# led_button.net
KiCad netlist of a schematic drawn in EAGLE
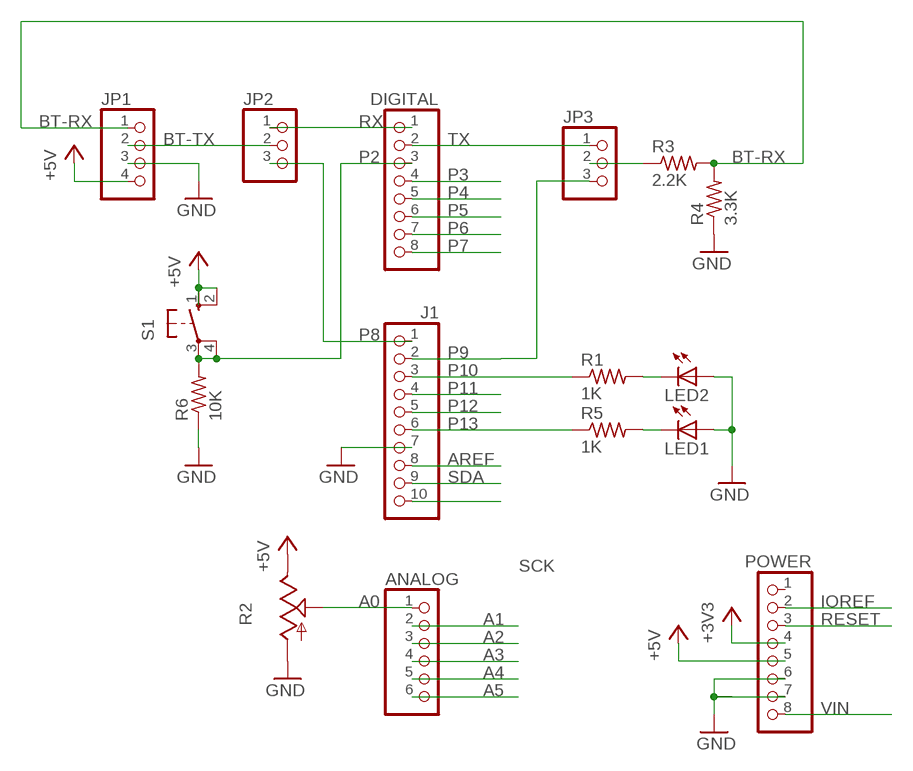
[diagram p0: schematic, sheet 1]

(export (version "E")
  (design (tool "Eeschema 10.0.6"))
  (components
    (comp (ref "ANALOG")
      (value "PINHD-1X6")
      (footprint "eagle-import:1X06")
      (libsource (lib "eagle-import") (part "PINHD-1X6"))
    )
    (comp (ref "DIGITAL")
      (value "PINHD-1X8TH")
      (footprint "eagle-import:1X08-TH")
      (libsource (lib "eagle-import") (part "PINHD-1X8TH"))
    )
    (comp (ref "J1")
      (value "PINHD-1X10TH")
      (footprint "eagle-import:1X10-TH")
      (libsource (lib "eagle-import") (part "PINHD-1X10TH"))
    )
    (comp (ref "JP1")
      (value "PINHD-1X4")
      (footprint "eagle-import:1X04")
      (libsource (lib "eagle-import") (part "PINHD-1X4"))
    )
    (comp (ref "JP2")
      (value "PINHD-1X3")
      (footprint "eagle-import:1X03")
      (libsource (lib "eagle-import") (part "PINHD-1X3"))
    )
    (comp (ref "JP3")
      (value "PINHD-1X3")
      (footprint "eagle-import:1X03")
      (libsource (lib "eagle-import") (part "PINHD-1X3"))
    )
    (comp (ref "LED1")
      (value "LED3MM")
      (footprint "eagle-import:LED3MM")
      (libsource (lib "eagle-import") (part "LED3MM"))
    )
    (comp (ref "LED2")
      (value "LED3MM")
      (footprint "eagle-import:LED3MM")
      (libsource (lib "eagle-import") (part "LED3MM"))
    )
    (comp (ref "POWER")
      (value "PINHD-1X8TH")
      (footprint "eagle-import:1X08-TH")
      (libsource (lib "eagle-import") (part "PINHD-1X8TH"))
    )
    (comp (ref "R1")
      (value "1K")
      (footprint "eagle-import:0207_10")
      (libsource (lib "eagle-import") (part "R-US_0207/10"))
    )
    (comp (ref "R2")
      (value "TRIM_US-B25P")
      (footprint "eagle-import:B25P")
      (libsource (lib "eagle-import") (part "TRIM_US-B25P"))
    )
    (comp (ref "R3")
      (value "2.2K")
      (footprint "eagle-import:0207_10")
      (libsource (lib "eagle-import") (part "R-US_0207/10"))
    )
    (comp (ref "R4")
      (value "3.3K")
      (footprint "eagle-import:0207_10")
      (libsource (lib "eagle-import") (part "R-US_0207/10"))
    )
    (comp (ref "R5")
      (value "1K")
      (footprint "eagle-import:0207_10")
      (libsource (lib "eagle-import") (part "R-US_0207/10"))
    )
    (comp (ref "R6")
      (value "10K")
      (footprint "eagle-import:0207_10")
      (libsource (lib "eagle-import") (part "R-US_0207/10"))
    )
    (comp (ref "S1")
      (value "10-XX")
      (footprint "eagle-import:B3F-10XX")
      (fields (field (name "MPN") "B3F-1000"))
      (libsource (lib "eagle-import") (part "10-XX"))
    )
  )
  (nets
    (net (code "1") (name "+3V3") (class "Default")
      (node (ref "POWER") (pin "4") (pinfunction "4_4") (pintype "passive"))
    )
    (net (code "2") (name "+5V") (class "Default")
      (node (ref "JP1") (pin "4") (pinfunction "4_4") (pintype "passive"))
      (node (ref "POWER") (pin "5") (pinfunction "5_5") (pintype "passive"))
      (node (ref "R2") (pin "E") (pinfunction "E_E") (pintype "passive"))
      (node (ref "S1") (pin "1") (pinfunction "S_1") (pintype "passive"))
      (node (ref "S1") (pin "2") (pinfunction "S1_2") (pintype "passive"))
    )
    (net (code "3") (name "/A0") (class "Default")
      (node (ref "ANALOG") (pin "1") (pinfunction "1_1") (pintype "passive"))
      (node (ref "R2") (pin "S") (pinfunction "S_S") (pintype "passive"))
    )
    (net (code "4") (name "/A1") (class "Default")
      (node (ref "ANALOG") (pin "2") (pinfunction "2_2") (pintype "passive"))
    )
    (net (code "5") (name "/A2") (class "Default")
      (node (ref "ANALOG") (pin "3") (pinfunction "3_3") (pintype "passive"))
    )
    (net (code "6") (name "/A3") (class "Default")
      (node (ref "ANALOG") (pin "4") (pinfunction "4_4") (pintype "passive"))
    )
    (net (code "7") (name "/A4") (class "Default")
      (node (ref "ANALOG") (pin "5") (pinfunction "5_5") (pintype "passive"))
    )
    (net (code "8") (name "/A5") (class "Default")
      (node (ref "ANALOG") (pin "6") (pinfunction "6_6") (pintype "passive"))
    )
    (net (code "9") (name "/AREF") (class "Default")
      (node (ref "J1") (pin "8") (pinfunction "8_8") (pintype "passive"))
    )
    (net (code "10") (name "/BT-RX") (class "Default")
      (node (ref "JP1") (pin "1") (pinfunction "1_1") (pintype "passive"))
      (node (ref "R3") (pin "2") (pinfunction "2_2") (pintype "passive"))
      (node (ref "R4") (pin "2") (pinfunction "2_2") (pintype "passive"))
    )
    (net (code "11") (name "/BT-TX") (class "Default")
      (node (ref "JP1") (pin "2") (pinfunction "2_2") (pintype "passive"))
      (node (ref "JP2") (pin "2") (pinfunction "2_2") (pintype "passive"))
    )
    (net (code "12") (name "/IOREF") (class "Default")
      (node (ref "POWER") (pin "2") (pinfunction "2_2") (pintype "passive"))
    )
    (net (code "13") (name "/P2") (class "Default")
      (node (ref "DIGITAL") (pin "3") (pinfunction "3_3") (pintype "passive"))
      (node (ref "R6") (pin "2") (pinfunction "2_2") (pintype "passive"))
      (node (ref "S1") (pin "3") (pinfunction "P_3") (pintype "passive"))
      (node (ref "S1") (pin "4") (pinfunction "P1_4") (pintype "passive"))
    )
    (net (code "14") (name "/P3") (class "Default")
      (node (ref "DIGITAL") (pin "4") (pinfunction "4_4") (pintype "passive"))
    )
    (net (code "15") (name "/P4") (class "Default")
      (node (ref "DIGITAL") (pin "5") (pinfunction "5_5") (pintype "passive"))
    )
    (net (code "16") (name "/P5") (class "Default")
      (node (ref "DIGITAL") (pin "6") (pinfunction "6_6") (pintype "passive"))
    )
    (net (code "17") (name "/P6") (class "Default")
      (node (ref "DIGITAL") (pin "7") (pinfunction "7_7") (pintype "passive"))
    )
    (net (code "18") (name "/P7") (class "Default")
      (node (ref "DIGITAL") (pin "8") (pinfunction "8_8") (pintype "passive"))
    )
    (net (code "19") (name "/P8") (class "Default")
      (node (ref "J1") (pin "1") (pinfunction "1_1") (pintype "passive"))
      (node (ref "JP2") (pin "3") (pinfunction "3_3") (pintype "passive"))
    )
    (net (code "20") (name "/P9") (class "Default")
      (node (ref "J1") (pin "2") (pinfunction "2_2") (pintype "passive"))
      (node (ref "JP3") (pin "3") (pinfunction "3_3") (pintype "passive"))
    )
    (net (code "21") (name "/P10") (class "Default")
      (node (ref "J1") (pin "3") (pinfunction "3_3") (pintype "passive"))
      (node (ref "R1") (pin "1") (pinfunction "1_1") (pintype "passive"))
    )
    (net (code "22") (name "/P11") (class "Default")
      (node (ref "J1") (pin "4") (pinfunction "4_4") (pintype "passive"))
    )
    (net (code "23") (name "/P12") (class "Default")
      (node (ref "J1") (pin "5") (pinfunction "5_5") (pintype "passive"))
    )
    (net (code "24") (name "/P13") (class "Default")
      (node (ref "J1") (pin "6") (pinfunction "6_6") (pintype "passive"))
      (node (ref "R5") (pin "1") (pinfunction "1_1") (pintype "passive"))
    )
    (net (code "25") (name "/RESET") (class "Default")
      (node (ref "POWER") (pin "3") (pinfunction "3_3") (pintype "passive"))
    )
    (net (code "26") (name "/RX") (class "Default")
      (node (ref "DIGITAL") (pin "1") (pinfunction "1_1") (pintype "passive"))
      (node (ref "JP2") (pin "1") (pinfunction "1_1") (pintype "passive"))
    )
    (net (code "27") (name "/SCK") (class "Default")
      (node (ref "J1") (pin "10") (pinfunction "10_10") (pintype "passive"))
    )
    (net (code "28") (name "/SDA") (class "Default")
      (node (ref "J1") (pin "9") (pinfunction "9_9") (pintype "passive"))
    )
    (net (code "29") (name "/TX") (class "Default")
      (node (ref "DIGITAL") (pin "2") (pinfunction "2_2") (pintype "passive"))
      (node (ref "JP3") (pin "1") (pinfunction "1_1") (pintype "passive"))
    )
    (net (code "30") (name "/VIN") (class "Default")
      (node (ref "POWER") (pin "8") (pinfunction "8_8") (pintype "passive"))
    )
    (net (code "31") (name "GND") (class "Default")
      (node (ref "J1") (pin "7") (pinfunction "7_7") (pintype "passive"))
      (node (ref "JP1") (pin "3") (pinfunction "3_3") (pintype "passive"))
      (node (ref "LED1") (pin "A") (pinfunction "A_A") (pintype "passive"))
      (node (ref "LED2") (pin "A") (pinfunction "A_A") (pintype "passive"))
      (node (ref "POWER") (pin "6") (pinfunction "6_6") (pintype "passive"))
      (node (ref "POWER") (pin "7") (pinfunction "7_7") (pintype "passive"))
      (node (ref "R2") (pin "A") (pinfunction "A_A") (pintype "passive"))
      (node (ref "R4") (pin "1") (pinfunction "1_1") (pintype "passive"))
      (node (ref "R6") (pin "1") (pinfunction "1_1") (pintype "passive"))
    )
    (net (code "32") (name "Net-(JP3-Pad2)") (class "Default")
      (node (ref "JP3") (pin "2") (pinfunction "2_2") (pintype "passive"))
      (node (ref "R3") (pin "1") (pinfunction "1_1") (pintype "passive"))
    )
    (net (code "33") (name "Net-(LED1-C)") (class "Default")
      (node (ref "LED1") (pin "K") (pinfunction "C_K") (pintype "passive"))
      (node (ref "R5") (pin "2") (pinfunction "2_2") (pintype "passive"))
    )
    (net (code "34") (name "Net-(LED2-C)") (class "Default")
      (node (ref "LED2") (pin "K") (pinfunction "C_K") (pintype "passive"))
      (node (ref "R1") (pin "2") (pinfunction "2_2") (pintype "passive"))
    )
    (net (code "35") (name "unconnected-(POWER-Pad1)") (class "Default")
      (node (ref "POWER") (pin "1") (pinfunction "1_1") (pintype "passive"))
    )
  )
)
